# SAFMC.net
KiCad netlist of a schematic drawn in EAGLE
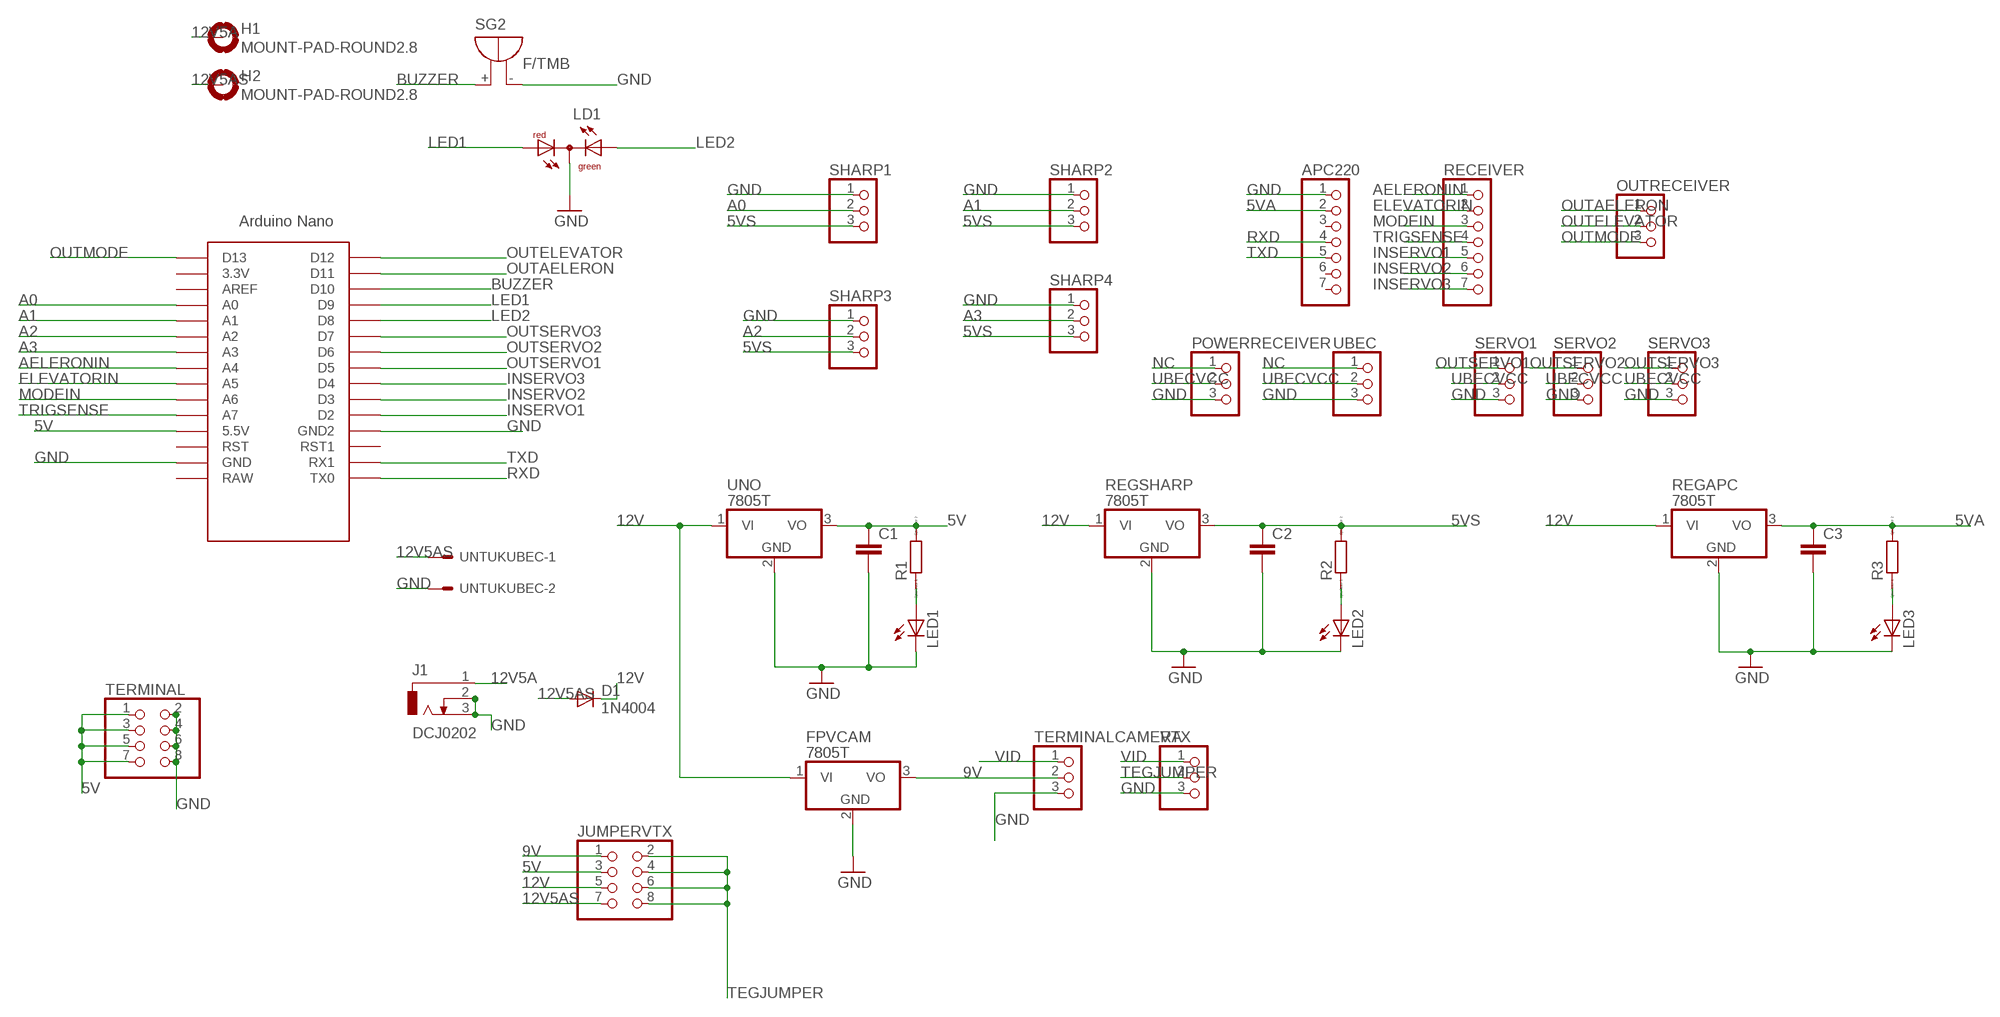
[diagram p0: schematic, sheet 1]

(export (version "E")
  (design (tool "Eeschema 10.0.6"))
  (components
    (comp (ref "APC220")
      (value "PINHD-1X7")
      (footprint "eagle-import:1X07")
      (libsource (lib "eagle-import") (part "PINHD-1X7"))
    )
    (comp (ref "C1")
      (value "C5/2.5")
      (footprint "eagle-import:C5B2.5")
      (libsource (lib "eagle-import") (part "C5/2.5"))
    )
    (comp (ref "C2")
      (value "C5/2.5")
      (footprint "eagle-import:C5B2.5")
      (libsource (lib "eagle-import") (part "C5/2.5"))
    )
    (comp (ref "C3")
      (value "C5/2.5")
      (footprint "eagle-import:C5B2.5")
      (libsource (lib "eagle-import") (part "C5/2.5"))
    )
    (comp (ref "D1")
      (value "1N4004")
      (footprint "eagle-import:DO41-10")
      (libsource (lib "eagle-import") (part "1N4004"))
    )
    (comp (ref "FPVCAM")
      (value "7805T")
      (footprint "eagle-import:TO220H")
      (libsource (lib "eagle-import") (part "78T05"))
    )
    (comp (ref "H1")
      (value "MOUNT-PAD-ROUND2.8")
      (footprint "eagle-import:2,8-PAD")
      (libsource (lib "eagle-import") (part "MOUNT-PAD-ROUND2.8"))
    )
    (comp (ref "H2")
      (value "MOUNT-PAD-ROUND2.8")
      (footprint "eagle-import:2,8-PAD")
      (libsource (lib "eagle-import") (part "MOUNT-PAD-ROUND2.8"))
    )
    (comp (ref "J1")
      (value "DCJ0202")
      (footprint "eagle-import:DCJ0202")
      (libsource (lib "eagle-import") (part "DCJ0202"))
    )
    (comp (ref "JUMPERVTX")
      (value "PINHD-2X4")
      (footprint "eagle-import:2X04")
      (libsource (lib "eagle-import") (part "PINHD-2X4"))
    )
    (comp (ref "LD1")
      (value "DUOLED-RG-C")
      (footprint "eagle-import:DUOLED-C-5MM")
      (libsource (lib "eagle-import") (part "DUOLED-RG-C"))
    )
    (comp (ref "LED1")
      (value "LED5MM")
      (footprint "eagle-import:LED5MM")
      (libsource (lib "eagle-import") (part "LED5MM"))
    )
    (comp (ref "LED2")
      (value "LED5MM")
      (footprint "eagle-import:LED5MM")
      (libsource (lib "eagle-import") (part "LED5MM"))
    )
    (comp (ref "LED3")
      (value "LED5MM")
      (footprint "eagle-import:LED5MM")
      (libsource (lib "eagle-import") (part "LED5MM"))
    )
    (comp (ref "OUTRECEIVER")
      (value "PINHD-1X3")
      (footprint "eagle-import:1X03")
      (libsource (lib "eagle-import") (part "PINHD-1X3"))
    )
    (comp (ref "POWERRECEIVER")
      (value "PINHD-1X3")
      (footprint "eagle-import:1X03")
      (libsource (lib "eagle-import") (part "PINHD-1X3"))
    )
    (comp (ref "R1")
      (value "R0204/7")
      (footprint "eagle-import:0204_7")
      (libsource (lib "eagle-import") (part "R0204/7"))
    )
    (comp (ref "R2")
      (value "R0204/7")
      (footprint "eagle-import:0204_7")
      (fields (field (name "SPICEMODEL") "NONE") (field (name "SPICEPREFIX") "R"))
      (libsource (lib "eagle-import") (part "R0204/7"))
    )
    (comp (ref "R3")
      (value "R0204/7")
      (footprint "eagle-import:0204_7")
      (fields (field (name "SPICEMODEL") "NONE") (field (name "SPICEPREFIX") "R"))
      (libsource (lib "eagle-import") (part "R0204/7"))
    )
    (comp (ref "RECEIVER")
      (value "PINHD-1X7")
      (footprint "eagle-import:1X07")
      (libsource (lib "eagle-import") (part "PINHD-1X7"))
    )
    (comp (ref "REGAPC")
      (value "7805T")
      (footprint "eagle-import:TO220H")
      (libsource (lib "eagle-import") (part "78T05"))
    )
    (comp (ref "REGSHARP")
      (value "7805T")
      (footprint "eagle-import:TO220H")
      (libsource (lib "eagle-import") (part "78T05"))
    )
    (comp (ref "SERVO1")
      (value "PINHD-1X3")
      (footprint "eagle-import:1X03")
      (libsource (lib "eagle-import") (part "PINHD-1X3"))
    )
    (comp (ref "SERVO2")
      (value "PINHD-1X3")
      (footprint "eagle-import:1X03")
      (libsource (lib "eagle-import") (part "PINHD-1X3"))
    )
    (comp (ref "SERVO3")
      (value "PINHD-1X3")
      (footprint "eagle-import:1X03")
      (libsource (lib "eagle-import") (part "PINHD-1X3"))
    )
    (comp (ref "SG2")
      (value "F/TMB")
      (footprint "eagle-import:F_TMB")
      (libsource (lib "eagle-import") (part "F/TMB"))
    )
    (comp (ref "SHARP1")
      (value "PINHD-1X3")
      (footprint "eagle-import:1X03")
      (libsource (lib "eagle-import") (part "PINHD-1X3"))
    )
    (comp (ref "SHARP2")
      (value "PINHD-1X3")
      (footprint "eagle-import:1X03")
      (libsource (lib "eagle-import") (part "PINHD-1X3"))
    )
    (comp (ref "SHARP3")
      (value "PINHD-1X3")
      (footprint "eagle-import:1X03")
      (libsource (lib "eagle-import") (part "PINHD-1X3"))
    )
    (comp (ref "SHARP4")
      (value "PINHD-1X3")
      (footprint "eagle-import:1X03")
      (libsource (lib "eagle-import") (part "PINHD-1X3"))
    )
    (comp (ref "TERMINAL")
      (value "PINHD-2X4")
      (footprint "eagle-import:2X04")
      (libsource (lib "eagle-import") (part "PINHD-2X4"))
    )
    (comp (ref "TERMINALCAMERA")
      (value "PINHD-1X3")
      (footprint "eagle-import:1X03")
      (libsource (lib "eagle-import") (part "PINHD-1X3"))
    )
    (comp (ref "U$2")
      (value "NANO")
      (footprint "eagle-import:NANO")
      (libsource (lib "eagle-import") (part "NANO"))
    )
    (comp (ref "UBEC")
      (value "PINHD-1X3")
      (footprint "eagle-import:1X03")
      (libsource (lib "eagle-import") (part "PINHD-1X3"))
    )
    (comp (ref "UNO")
      (value "7805T")
      (footprint "eagle-import:TO220H")
      (libsource (lib "eagle-import") (part "78T05"))
    )
    (comp (ref "UNTUKUBEC")
      (value "KK-156-2")
      (footprint "eagle-import:KK-156-2")
      (libsource (lib "eagle-import") (part "KK-156-2"))
    )
    (comp (ref "VTX")
      (value "PINHD-1X3")
      (footprint "eagle-import:1X03")
      (libsource (lib "eagle-import") (part "PINHD-1X3"))
    )
  )
  (nets
    (net (code "1") (name "/5V") (class "Default")
      (node (ref "C1") (pin "1") (pinfunction "1_1") (pintype "passive"))
      (node (ref "JUMPERVTX") (pin "3") (pinfunction "3_3") (pintype "passive"))
      (node (ref "R1") (pin "2") (pinfunction "2_2") (pintype "passive"))
      (node (ref "TERMINAL") (pin "1") (pinfunction "1_1") (pintype "passive"))
      (node (ref "TERMINAL") (pin "3") (pinfunction "3_3") (pintype "passive"))
      (node (ref "TERMINAL") (pin "5") (pinfunction "5_5") (pintype "passive"))
      (node (ref "TERMINAL") (pin "7") (pinfunction "7_7") (pintype "passive"))
      (node (ref "U$2") (pin "5V") (pinfunction "5.5V_5V") (pintype "bidirectional"))
      (node (ref "UNO") (pin "3") (pinfunction "VO_3") (pintype "passive"))
    )
    (net (code "2") (name "/5VA") (class "Default")
      (node (ref "APC220") (pin "2") (pinfunction "2_2") (pintype "passive"))
      (node (ref "C3") (pin "1") (pinfunction "1_1") (pintype "passive"))
      (node (ref "R3") (pin "2") (pinfunction "2_2") (pintype "passive"))
      (node (ref "REGAPC") (pin "3") (pinfunction "VO_3") (pintype "passive"))
    )
    (net (code "3") (name "/5VS") (class "Default")
      (node (ref "C2") (pin "1") (pinfunction "1_1") (pintype "passive"))
      (node (ref "R2") (pin "2") (pinfunction "2_2") (pintype "passive"))
      (node (ref "REGSHARP") (pin "3") (pinfunction "VO_3") (pintype "passive"))
      (node (ref "SHARP1") (pin "3") (pinfunction "3_3") (pintype "passive"))
      (node (ref "SHARP2") (pin "3") (pinfunction "3_3") (pintype "passive"))
      (node (ref "SHARP3") (pin "3") (pinfunction "3_3") (pintype "passive"))
      (node (ref "SHARP4") (pin "3") (pinfunction "3_3") (pintype "passive"))
    )
    (net (code "4") (name "/9V") (class "Default")
      (node (ref "FPVCAM") (pin "3") (pinfunction "VO_3") (pintype "passive"))
      (node (ref "JUMPERVTX") (pin "1") (pinfunction "1_1") (pintype "passive"))
      (node (ref "TERMINALCAMERA") (pin "2") (pinfunction "2_2") (pintype "passive"))
    )
    (net (code "5") (name "/12V") (class "Default")
      (node (ref "D1") (pin "C") (pinfunction "C_C") (pintype "passive"))
      (node (ref "FPVCAM") (pin "1") (pinfunction "VI_1") (pintype "input"))
      (node (ref "JUMPERVTX") (pin "5") (pinfunction "5_5") (pintype "passive"))
      (node (ref "REGAPC") (pin "1") (pinfunction "VI_1") (pintype "input"))
      (node (ref "REGSHARP") (pin "1") (pinfunction "VI_1") (pintype "input"))
      (node (ref "UNO") (pin "1") (pinfunction "VI_1") (pintype "input"))
    )
    (net (code "6") (name "/12V5A") (class "Default")
      (node (ref "H1") (pin "B2,8") (pinfunction "MOUNT_B2,8") (pintype "passive"))
      (node (ref "J1") (pin "1") (pinfunction "1_1") (pintype "passive"))
    )
    (net (code "7") (name "/12V5AS") (class "Default")
      (node (ref "D1") (pin "A") (pinfunction "A_A") (pintype "passive"))
      (node (ref "H2") (pin "B2,8") (pinfunction "MOUNT_B2,8") (pintype "passive"))
      (node (ref "JUMPERVTX") (pin "7") (pinfunction "7_7") (pintype "passive"))
      (node (ref "UNTUKUBEC") (pin "1") (pinfunction "S_1") (pintype "passive"))
    )
    (net (code "8") (name "/A0") (class "Default")
      (node (ref "SHARP1") (pin "2") (pinfunction "2_2") (pintype "passive"))
      (node (ref "U$2") (pin "A0") (pinfunction "A0_A0") (pintype "bidirectional"))
    )
    (net (code "9") (name "/A1") (class "Default")
      (node (ref "SHARP2") (pin "2") (pinfunction "2_2") (pintype "passive"))
      (node (ref "U$2") (pin "A1") (pinfunction "A1_A1") (pintype "bidirectional"))
    )
    (net (code "10") (name "/A2") (class "Default")
      (node (ref "SHARP3") (pin "2") (pinfunction "2_2") (pintype "passive"))
      (node (ref "U$2") (pin "A2") (pinfunction "A2_A2") (pintype "bidirectional"))
    )
    (net (code "11") (name "/A3") (class "Default")
      (node (ref "SHARP4") (pin "2") (pinfunction "2_2") (pintype "passive"))
      (node (ref "U$2") (pin "A3") (pinfunction "A3_A3") (pintype "bidirectional"))
    )
    (net (code "12") (name "/AELERONIN") (class "Default")
      (node (ref "RECEIVER") (pin "1") (pinfunction "1_1") (pintype "passive"))
      (node (ref "U$2") (pin "A4") (pinfunction "A4_A4") (pintype "bidirectional"))
    )
    (net (code "13") (name "/BUZZER") (class "Default")
      (node (ref "SG2") (pin "+") (pinfunction "+_+") (pintype "passive"))
      (node (ref "U$2") (pin "D10") (pinfunction "D10_D10") (pintype "bidirectional"))
    )
    (net (code "14") (name "/ELEVATORIN") (class "Default")
      (node (ref "RECEIVER") (pin "2") (pinfunction "2_2") (pintype "passive"))
      (node (ref "U$2") (pin "A5") (pinfunction "A5_A5") (pintype "bidirectional"))
    )
    (net (code "15") (name "/INSERVO1") (class "Default")
      (node (ref "RECEIVER") (pin "5") (pinfunction "5_5") (pintype "passive"))
      (node (ref "U$2") (pin "D2") (pinfunction "D2_D2") (pintype "bidirectional"))
    )
    (net (code "16") (name "/INSERVO2") (class "Default")
      (node (ref "RECEIVER") (pin "6") (pinfunction "6_6") (pintype "passive"))
      (node (ref "U$2") (pin "D3") (pinfunction "D3_D3") (pintype "bidirectional"))
    )
    (net (code "17") (name "/INSERVO3") (class "Default")
      (node (ref "RECEIVER") (pin "7") (pinfunction "7_7") (pintype "passive"))
      (node (ref "U$2") (pin "D4") (pinfunction "D4_D4") (pintype "bidirectional"))
    )
    (net (code "18") (name "/LED1") (class "Default")
      (node (ref "LD1") (pin "AR") (pinfunction "AR_AR") (pintype "passive"))
      (node (ref "U$2") (pin "D9") (pinfunction "D9_D9") (pintype "bidirectional"))
    )
    (net (code "19") (name "/LED2") (class "Default")
      (node (ref "LD1") (pin "AX") (pinfunction "AG_AX") (pintype "passive"))
      (node (ref "U$2") (pin "D8") (pinfunction "D8_D8") (pintype "bidirectional"))
    )
    (net (code "20") (name "/MODEIN") (class "Default")
      (node (ref "RECEIVER") (pin "3") (pinfunction "3_3") (pintype "passive"))
      (node (ref "U$2") (pin "A6") (pinfunction "A6_A6") (pintype "bidirectional"))
    )
    (net (code "21") (name "/NC") (class "Default")
      (node (ref "POWERRECEIVER") (pin "1") (pinfunction "1_1") (pintype "passive"))
      (node (ref "UBEC") (pin "1") (pinfunction "1_1") (pintype "passive"))
    )
    (net (code "22") (name "/OUTAELERON") (class "Default")
      (node (ref "OUTRECEIVER") (pin "1") (pinfunction "1_1") (pintype "passive"))
      (node (ref "U$2") (pin "D11") (pinfunction "D11_D11") (pintype "bidirectional"))
    )
    (net (code "23") (name "/OUTELEVATOR") (class "Default")
      (node (ref "OUTRECEIVER") (pin "2") (pinfunction "2_2") (pintype "passive"))
      (node (ref "U$2") (pin "D12") (pinfunction "D12_D12") (pintype "bidirectional"))
    )
    (net (code "24") (name "/OUTMODE") (class "Default")
      (node (ref "OUTRECEIVER") (pin "3") (pinfunction "3_3") (pintype "passive"))
      (node (ref "U$2") (pin "D13") (pinfunction "D13_D13") (pintype "bidirectional"))
    )
    (net (code "25") (name "/OUTSERVO1") (class "Default")
      (node (ref "SERVO1") (pin "1") (pinfunction "1_1") (pintype "passive"))
      (node (ref "U$2") (pin "D5") (pinfunction "D5_D5") (pintype "bidirectional"))
    )
    (net (code "26") (name "/OUTSERVO2") (class "Default")
      (node (ref "SERVO2") (pin "1") (pinfunction "1_1") (pintype "passive"))
      (node (ref "U$2") (pin "D6") (pinfunction "D6_D6") (pintype "bidirectional"))
    )
    (net (code "27") (name "/OUTSERVO3") (class "Default")
      (node (ref "SERVO3") (pin "1") (pinfunction "1_1") (pintype "passive"))
      (node (ref "U$2") (pin "D7") (pinfunction "D7_D7") (pintype "bidirectional"))
    )
    (net (code "28") (name "/RXD") (class "Default")
      (node (ref "APC220") (pin "4") (pinfunction "4_4") (pintype "passive"))
      (node (ref "U$2") (pin "TX0") (pinfunction "TX0_TX0") (pintype "bidirectional"))
    )
    (net (code "29") (name "/TEGJUMPER") (class "Default")
      (node (ref "JUMPERVTX") (pin "2") (pinfunction "2_2") (pintype "passive"))
      (node (ref "JUMPERVTX") (pin "4") (pinfunction "4_4") (pintype "passive"))
      (node (ref "JUMPERVTX") (pin "6") (pinfunction "6_6") (pintype "passive"))
      (node (ref "JUMPERVTX") (pin "8") (pinfunction "8_8") (pintype "passive"))
      (node (ref "VTX") (pin "2") (pinfunction "2_2") (pintype "passive"))
    )
    (net (code "30") (name "/TRIGSENSE") (class "Default")
      (node (ref "RECEIVER") (pin "4") (pinfunction "4_4") (pintype "passive"))
      (node (ref "U$2") (pin "A7") (pinfunction "A7_A7") (pintype "bidirectional"))
    )
    (net (code "31") (name "/TXD") (class "Default")
      (node (ref "APC220") (pin "5") (pinfunction "5_5") (pintype "passive"))
      (node (ref "U$2") (pin "RX1") (pinfunction "RX1_RX1") (pintype "bidirectional"))
    )
    (net (code "32") (name "/UBECVCC") (class "Default")
      (node (ref "POWERRECEIVER") (pin "2") (pinfunction "2_2") (pintype "passive"))
      (node (ref "SERVO1") (pin "2") (pinfunction "2_2") (pintype "passive"))
      (node (ref "SERVO2") (pin "2") (pinfunction "2_2") (pintype "passive"))
      (node (ref "SERVO3") (pin "2") (pinfunction "2_2") (pintype "passive"))
      (node (ref "UBEC") (pin "2") (pinfunction "2_2") (pintype "passive"))
    )
    (net (code "33") (name "/VID") (class "Default")
      (node (ref "TERMINALCAMERA") (pin "1") (pinfunction "1_1") (pintype "passive"))
      (node (ref "VTX") (pin "1") (pinfunction "1_1") (pintype "passive"))
    )
    (net (code "34") (name "GND") (class "Default")
      (node (ref "APC220") (pin "1") (pinfunction "1_1") (pintype "passive"))
      (node (ref "C1") (pin "2") (pinfunction "2_2") (pintype "passive"))
      (node (ref "C2") (pin "2") (pinfunction "2_2") (pintype "passive"))
      (node (ref "C3") (pin "2") (pinfunction "2_2") (pintype "passive"))
      (node (ref "FPVCAM") (pin "2") (pinfunction "GND_2") (pintype "passive"))
      (node (ref "J1") (pin "2") (pinfunction "2_2") (pintype "passive"))
      (node (ref "J1") (pin "3") (pinfunction "3_3") (pintype "passive"))
      (node (ref "LD1") (pin "C") (pinfunction "C_C") (pintype "passive"))
      (node (ref "LED1") (pin "K") (pinfunction "C_K") (pintype "passive"))
      (node (ref "LED2") (pin "K") (pinfunction "C_K") (pintype "passive"))
      (node (ref "LED3") (pin "K") (pinfunction "C_K") (pintype "passive"))
      (node (ref "POWERRECEIVER") (pin "3") (pinfunction "3_3") (pintype "passive"))
      (node (ref "REGAPC") (pin "2") (pinfunction "GND_2") (pintype "passive"))
      (node (ref "REGSHARP") (pin "2") (pinfunction "GND_2") (pintype "passive"))
      (node (ref "SERVO1") (pin "3") (pinfunction "3_3") (pintype "passive"))
      (node (ref "SERVO2") (pin "3") (pinfunction "3_3") (pintype "passive"))
      (node (ref "SERVO3") (pin "3") (pinfunction "3_3") (pintype "passive"))
      (node (ref "SG2") (pin "-") (pinfunction "-_-") (pintype "passive"))
      (node (ref "SHARP1") (pin "1") (pinfunction "1_1") (pintype "passive"))
      (node (ref "SHARP2") (pin "1") (pinfunction "1_1") (pintype "passive"))
      (node (ref "SHARP3") (pin "1") (pinfunction "1_1") (pintype "passive"))
      (node (ref "SHARP4") (pin "1") (pinfunction "1_1") (pintype "passive"))
      (node (ref "TERMINAL") (pin "2") (pinfunction "2_2") (pintype "passive"))
      (node (ref "TERMINAL") (pin "4") (pinfunction "4_4") (pintype "passive"))
      (node (ref "TERMINAL") (pin "6") (pinfunction "6_6") (pintype "passive"))
      (node (ref "TERMINAL") (pin "8") (pinfunction "8_8") (pintype "passive"))
      (node (ref "TERMINALCAMERA") (pin "3") (pinfunction "3_3") (pintype "passive"))
      (node (ref "U$2") (pin "GND") (pinfunction "GND_GND") (pintype "bidirectional"))
      (node (ref "U$2") (pin "GND1") (pinfunction "GND2_GND1") (pintype "bidirectional"))
      (node (ref "UBEC") (pin "3") (pinfunction "3_3") (pintype "passive"))
      (node (ref "UNO") (pin "2") (pinfunction "GND_2") (pintype "passive"))
      (node (ref "UNTUKUBEC") (pin "2") (pinfunction "S_2") (pintype "passive"))
      (node (ref "VTX") (pin "3") (pinfunction "3_3") (pintype "passive"))
    )
    (net (code "35") (name "Net-(LED1-PadA)") (class "Default")
      (node (ref "LED1") (pin "A") (pinfunction "A_A") (pintype "passive"))
      (node (ref "R1") (pin "1") (pinfunction "1_1") (pintype "passive"))
    )
    (net (code "36") (name "Net-(LED2-PadA)") (class "Default")
      (node (ref "LED2") (pin "A") (pinfunction "A_A") (pintype "passive"))
      (node (ref "R2") (pin "1") (pinfunction "1_1") (pintype "passive"))
    )
    (net (code "37") (name "Net-(LED3-PadA)") (class "Default")
      (node (ref "LED3") (pin "A") (pinfunction "A_A") (pintype "passive"))
      (node (ref "R3") (pin "1") (pinfunction "1_1") (pintype "passive"))
    )
    (net (code "38") (name "unconnected-(APC220-Pad3)") (class "Default")
      (node (ref "APC220") (pin "3") (pinfunction "3_3") (pintype "passive"))
    )
    (net (code "39") (name "unconnected-(APC220-Pad6)") (class "Default")
      (node (ref "APC220") (pin "6") (pinfunction "6_6") (pintype "passive"))
    )
    (net (code "40") (name "unconnected-(APC220-Pad7)") (class "Default")
      (node (ref "APC220") (pin "7") (pinfunction "7_7") (pintype "passive"))
    )
    (net (code "41") (name "unconnected-(U$2-Pad3.3V)") (class "Default")
      (node (ref "U$2") (pin "3.3V") (pinfunction "3.3V_3.3V") (pintype "bidirectional"))
    )
    (net (code "42") (name "unconnected-(U$2-PadAREF)") (class "Default")
      (node (ref "U$2") (pin "AREF") (pinfunction "AREF_AREF") (pintype "bidirectional"))
    )
    (net (code "43") (name "unconnected-(U$2-PadICSP1)") (class "Default")
      (node (ref "U$2") (pin "ICSP1") (pinfunction "ICSP1_ICSP1") (pintype "bidirectional"))
    )
    (net (code "44") (name "unconnected-(U$2-PadICSP2)") (class "Default")
      (node (ref "U$2") (pin "ICSP2") (pinfunction "ICSP2_ICSP2") (pintype "bidirectional"))
    )
    (net (code "45") (name "unconnected-(U$2-PadICSP3)") (class "Default")
      (node (ref "U$2") (pin "ICSP3") (pinfunction "ICSP3_ICSP3") (pintype "bidirectional"))
    )
    (net (code "46") (name "unconnected-(U$2-PadICSP4)") (class "Default")
      (node (ref "U$2") (pin "ICSP4") (pinfunction "ICSP4_ICSP4") (pintype "bidirectional"))
    )
    (net (code "47") (name "unconnected-(U$2-PadICSP5)") (class "Default")
      (node (ref "U$2") (pin "ICSP5") (pinfunction "ICSP5_ICSP5") (pintype "bidirectional"))
    )
    (net (code "48") (name "unconnected-(U$2-PadICSP6)") (class "Default")
      (node (ref "U$2") (pin "ICSP6") (pinfunction "ICSP6_ICSP6") (pintype "bidirectional"))
    )
    (net (code "49") (name "unconnected-(U$2-PadRAW)") (class "Default")
      (node (ref "U$2") (pin "RAW") (pinfunction "RAW_RAW") (pintype "bidirectional"))
    )
    (net (code "50") (name "unconnected-(U$2-PadRST)") (class "Default")
      (node (ref "U$2") (pin "RST") (pinfunction "RST_RST") (pintype "bidirectional"))
    )
    (net (code "51") (name "unconnected-(U$2-PadRST1)") (class "Default")
      (node (ref "U$2") (pin "RST1") (pinfunction "RST1_RST1") (pintype "bidirectional"))
    )
  )
)
